# sap_flux-v22.net
KiCad netlist of a schematic drawn in EAGLE
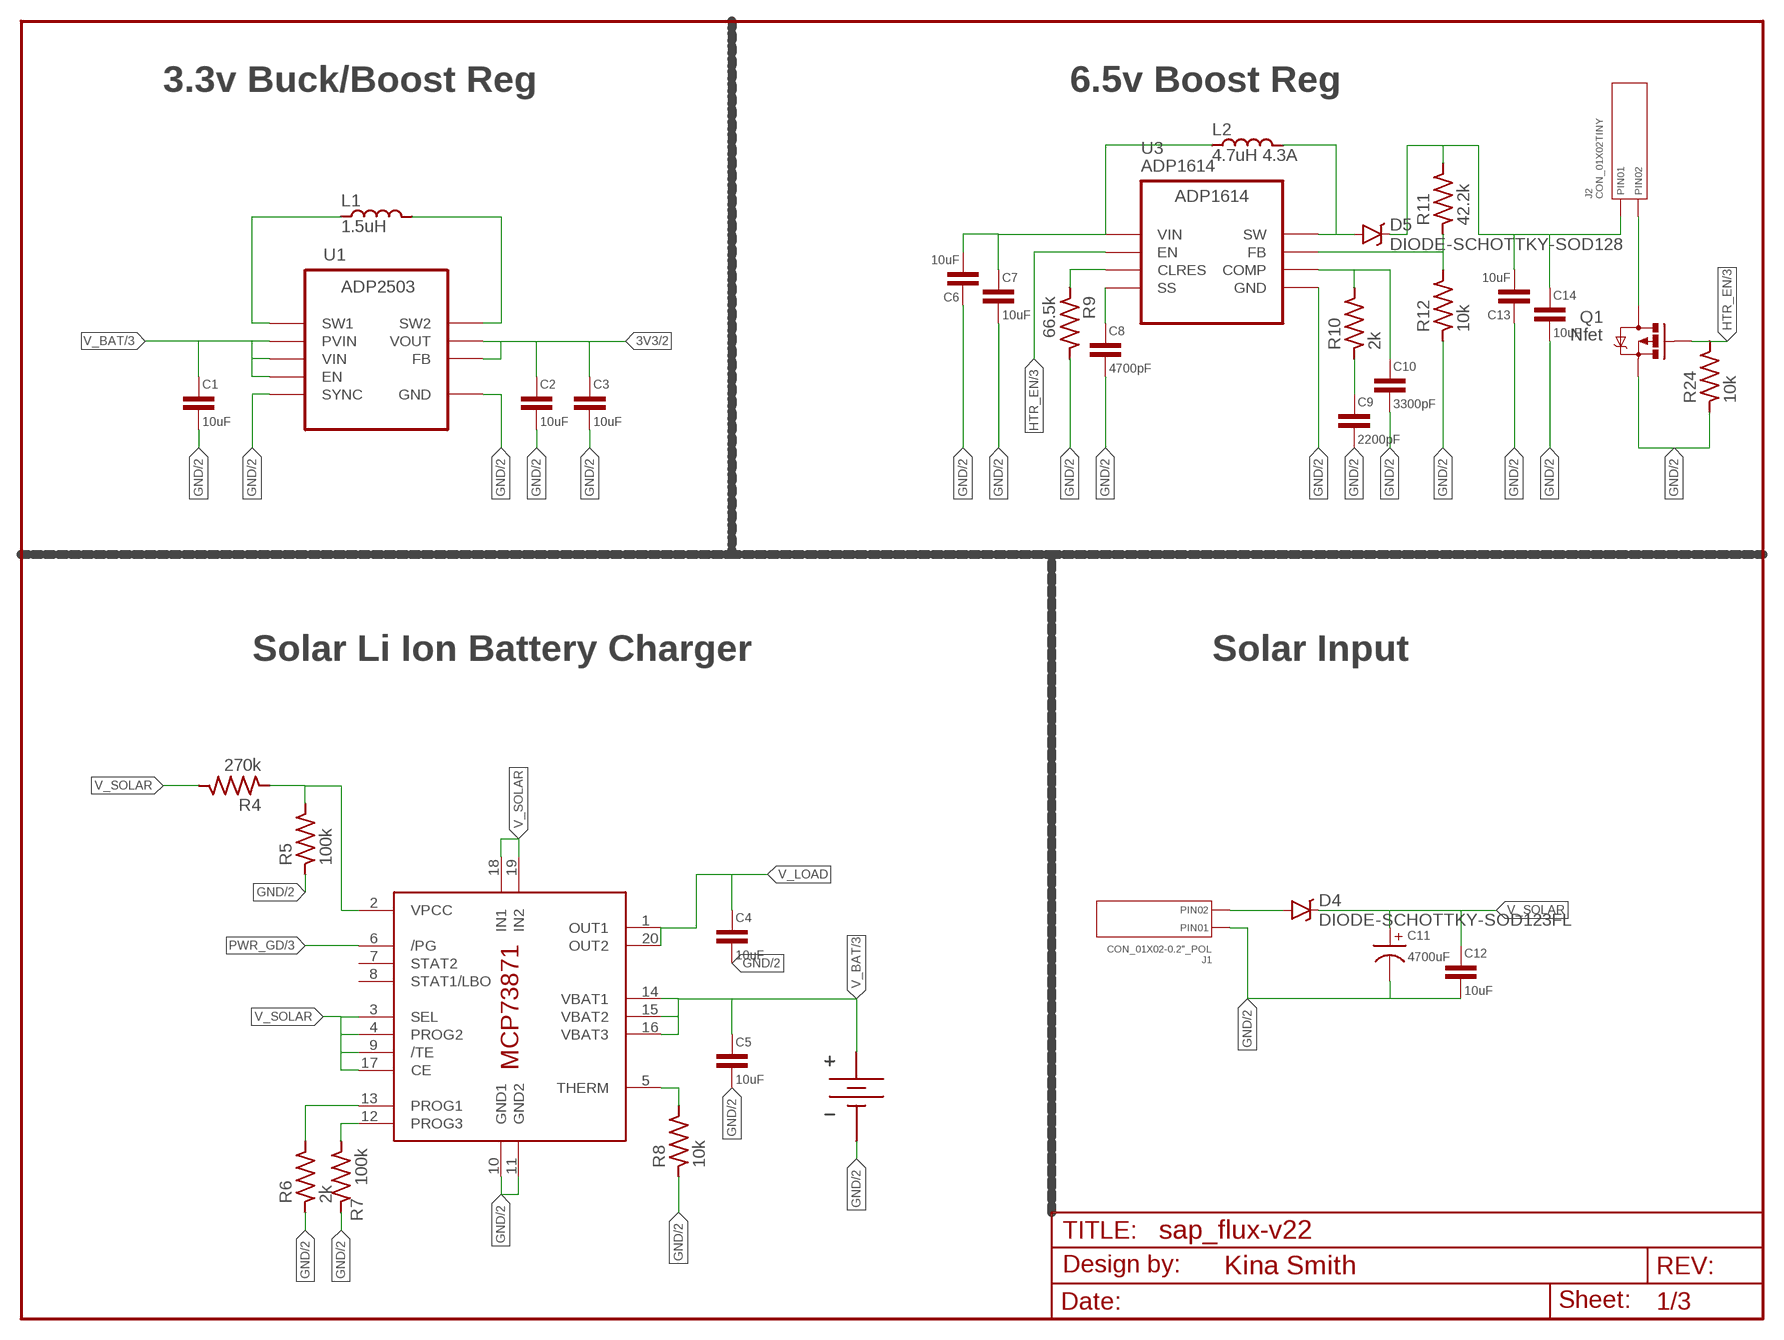
[diagram p0: schematic, sheet 1]
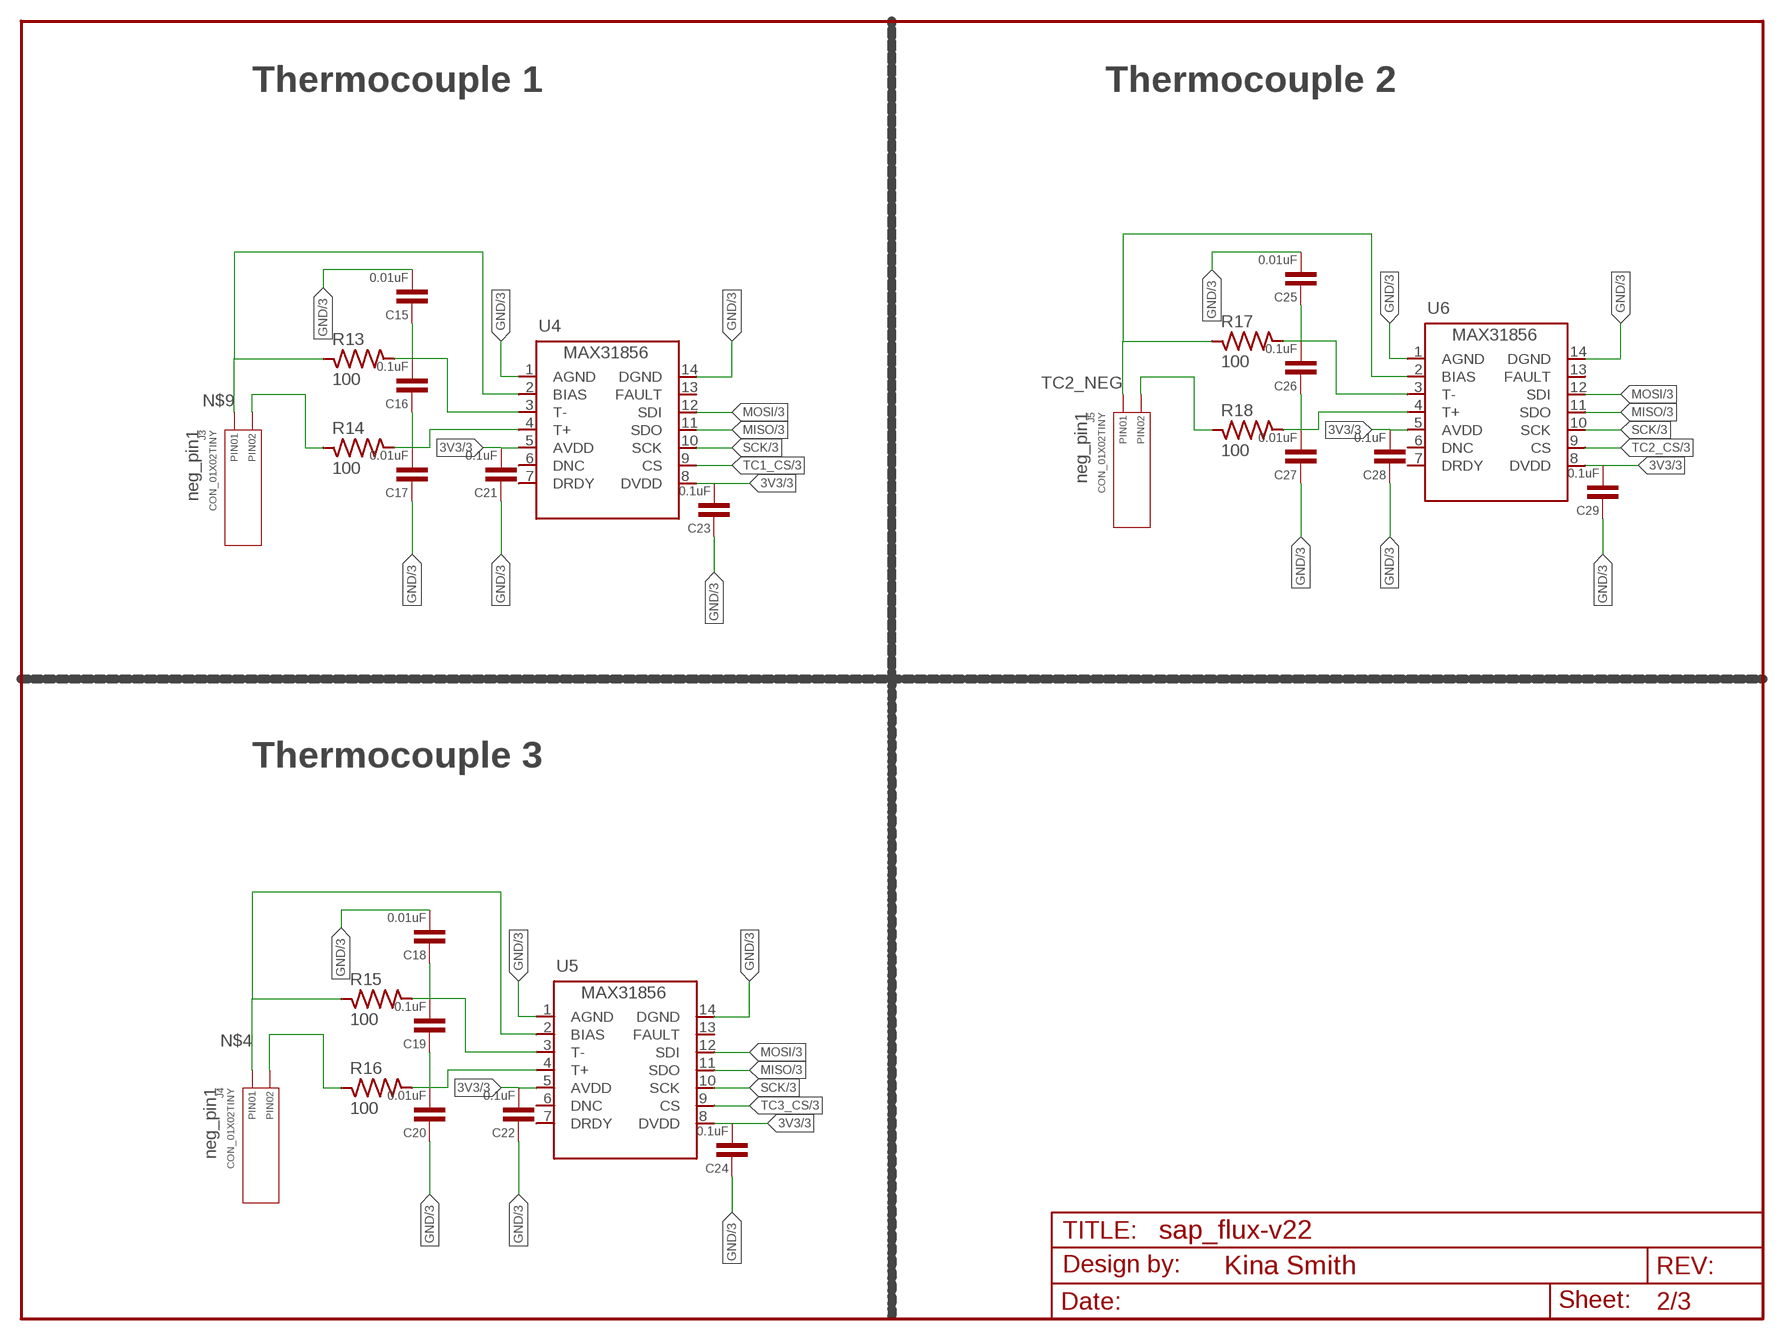
[diagram p1: schematic, sheet 2]
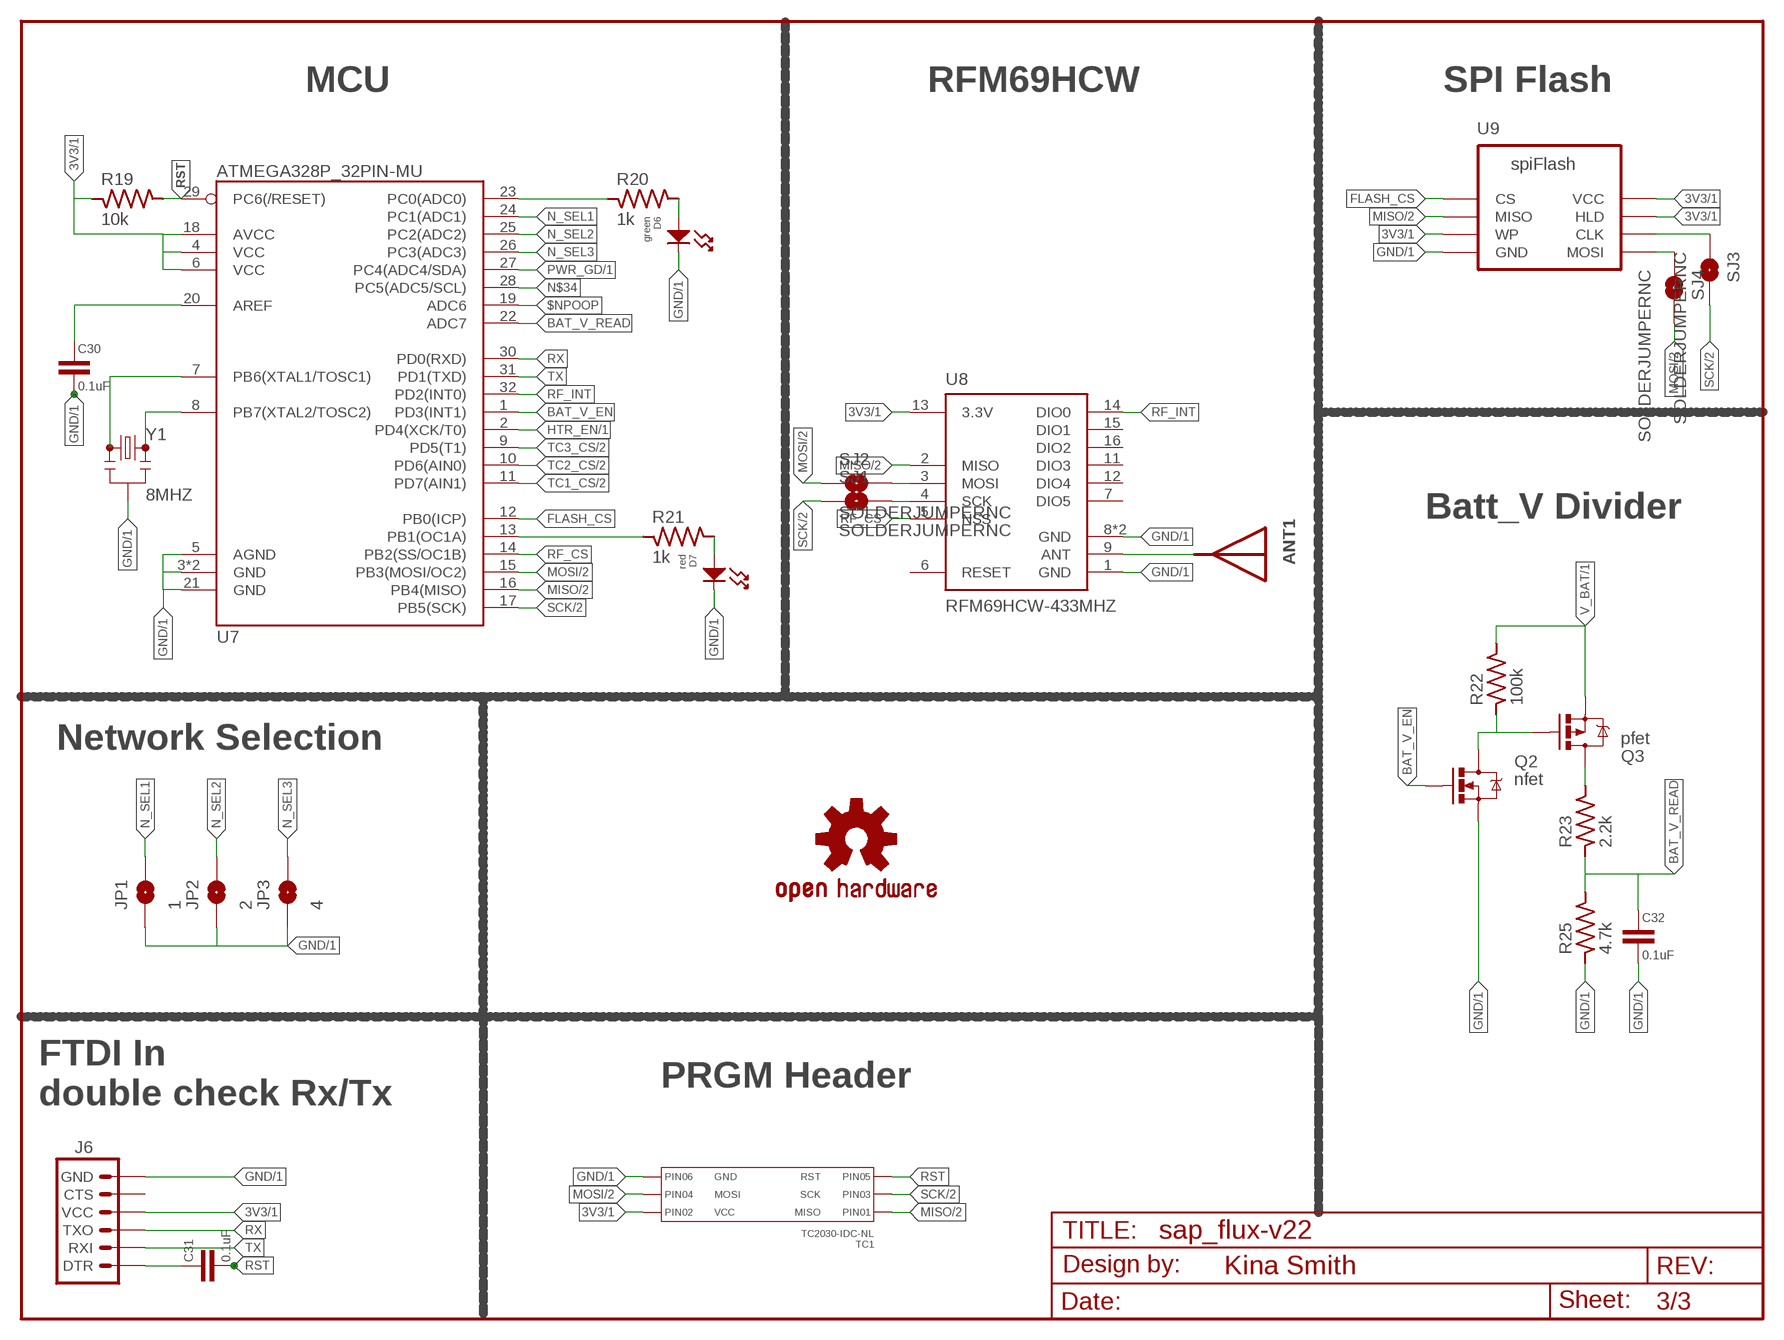
[diagram p2: schematic, sheet 3]

(export (version "E")
  (design (tool "Eeschema 10.0.6"))
  (components
    (comp (ref "BATT1")
      (value "BATTERY_HOLDER-18650_CLIP")
      (footprint "eagle-import:BAT_18650_CLIP")
      (fields (field (name "PARTNO") "54"))
      (libsource (lib "eagle-import") (part "BATTERY_HOLDER-18650_CLIP"))
    )
    (comp (ref "C1")
      (value "10uF")
      (footprint "eagle-import:C0805-N")
      (fields (field (name "PARTNO") "GRM21BR61C106KE15K"))
      (libsource (lib "eagle-import") (part "CAPACITOR_NP0805-N"))
    )
    (comp (ref "C2")
      (value "10uF")
      (footprint "eagle-import:C0805-N")
      (fields (field (name "PARTNO") "GRM21BR61C106KE15K"))
      (libsource (lib "eagle-import") (part "CAPACITOR_NP0805-N"))
    )
    (comp (ref "C3")
      (value "10uF")
      (footprint "eagle-import:C0805-N")
      (fields (field (name "PARTNO") "GRM21BR61C106KE15K"))
      (libsource (lib "eagle-import") (part "CAPACITOR_NP0805-N"))
    )
    (comp (ref "C4")
      (value "10uF")
      (footprint "eagle-import:C0805-N")
      (fields (field (name "PARTNO") "GRM21BR61C106KE15K"))
      (libsource (lib "eagle-import") (part "CAPACITOR_NP0805-N"))
    )
    (comp (ref "C5")
      (value "10uF")
      (footprint "eagle-import:C0805-N")
      (fields (field (name "PARTNO") "GRM21BR61C106KE15K"))
      (libsource (lib "eagle-import") (part "CAPACITOR_NP0805-N"))
    )
    (comp (ref "C6")
      (value "10uF")
      (footprint "eagle-import:C0805-N")
      (fields (field (name "PARTNO") "GRM21BR61C106KE15K"))
      (libsource (lib "eagle-import") (part "CAPACITOR_NP0805-N"))
    )
    (comp (ref "C7")
      (value "10uF")
      (footprint "eagle-import:C0805-N")
      (fields (field (name "PARTNO") "GRM21BR61C106KE15K"))
      (libsource (lib "eagle-import") (part "CAPACITOR_NP0805-N"))
    )
    (comp (ref "C8")
      (value "4700pF")
      (footprint "eagle-import:C0603-N")
      (fields (field (name "PARTNO") "GRM188R71C472KA01D"))
      (libsource (lib "eagle-import") (part "CAPACITOR_NP0603-N"))
    )
    (comp (ref "C9")
      (value "2200pF")
      (footprint "eagle-import:C0603-N")
      (fields (field (name "PARTNO") "GRM188R71C222KA01D"))
      (libsource (lib "eagle-import") (part "CAPACITOR_NP0603-N"))
    )
    (comp (ref "C10")
      (value "3300pF")
      (footprint "eagle-import:C0603-N")
      (fields (field (name "PARTNO") "C0603C332K4RACTU"))
      (libsource (lib "eagle-import") (part "CAPACITOR_NP0603-N"))
    )
    (comp (ref "C11")
      (value "4700uF")
      (footprint "eagle-import:CP_TH_5MM")
      (fields (field (name "PARTNO") "ECA-1AM472"))
      (libsource (lib "eagle-import") (part "CAPACITOR_P-TH_5MM"))
    )
    (comp (ref "C12")
      (value "10uF")
      (footprint "eagle-import:C0805-N")
      (fields (field (name "PARTNO") "GRM21BR61C106KE15K"))
      (libsource (lib "eagle-import") (part "CAPACITOR_NP0805-N"))
    )
    (comp (ref "C13")
      (value "10uF")
      (footprint "eagle-import:C0805-N")
      (fields (field (name "PARTNO") "GRM21BR61C106KE15K"))
      (libsource (lib "eagle-import") (part "CAPACITOR_NP0805-N"))
    )
    (comp (ref "C14")
      (value "10uF")
      (footprint "eagle-import:C0805-N")
      (fields (field (name "PARTNO") "GRM21BR61C106KE15K"))
      (libsource (lib "eagle-import") (part "CAPACITOR_NP0805-N"))
    )
    (comp (ref "D4")
      (value "DIODE-SCHOTTKY-SOD123FL")
      (footprint "eagle-import:SOD-123FL")
      (fields (field (name "PARTNO") "MBR120VLSFT1G"))
      (libsource (lib "eagle-import") (part "DIODE-SCHOTTKY-SOD123FL"))
    )
    (comp (ref "D5")
      (value "DIODE-SCHOTTKY-SOD128")
      (footprint "eagle-import:SOD128")
      (fields (field (name "PARTNO") "CMS05(TE12L,Q,M)"))
      (libsource (lib "eagle-import") (part "DIODE-SCHOTTKY-SOD128"))
    )
    (comp (ref "FRAME1")
      (value "FRAME-LETTER")
      (footprint "eagle-import:CREATIVE_COMMONS")
      (fields (field (name "PARTNO") "NA"))
      (libsource (lib "eagle-import") (part "FRAME-LETTER"))
    )
    (comp (ref "J1")
      (value "CON_01X02-0.2\"_POL")
      (footprint "eagle-import:1X02_SCREWTERM_0.2IN")
      (fields (field (name "PARTNO") "0398890042"))
      (libsource (lib "eagle-import") (part "CON_01X02-0.2{dblquote}_POL"))
    )
    (comp (ref "J2")
      (value "CON_01X02TINY")
      (footprint "eagle-import:1X02_TINY")
      (libsource (lib "eagle-import") (part "CON_01X02TINY"))
    )
    (comp (ref "L1")
      (value "1.5uH")
      (footprint "eagle-import:L3030")
      (fields (field (name "PARTNO") "NR3015T1R5N"))
      (libsource (lib "eagle-import") (part "INDUCTOR3030"))
    )
    (comp (ref "L2")
      (value "4.7uH 4.3A")
      (footprint "eagle-import:L8080")
      (fields (field (name "PARTNO") "NRS8040T100MJGJ"))
      (libsource (lib "eagle-import") (part "INDUCTOR8080"))
    )
    (comp (ref "Q1")
      (value "Nfet")
      (footprint "eagle-import:SOT23-3")
      (fields (field (name "PARTNO") "DMN2075U-7"))
      (libsource (lib "eagle-import") (part "MOSFET-PCHANNELSOT23-3"))
    )
    (comp (ref "R4")
      (value "270k")
      (footprint "eagle-import:R0603-N")
      (fields (field (name "PARTNO") "RC0603FR-07270KL"))
      (libsource (lib "eagle-import") (part "RESISTOR0603-N"))
    )
    (comp (ref "R5")
      (value "100k")
      (footprint "eagle-import:R0603-N")
      (fields (field (name "PARTNO") "RC0603FR-07100KL"))
      (libsource (lib "eagle-import") (part "RESISTOR0603-N"))
    )
    (comp (ref "R6")
      (value "2k")
      (footprint "eagle-import:R0603-N")
      (fields (field (name "PARTNO") "RC0603FR-072KL"))
      (libsource (lib "eagle-import") (part "RESISTOR0603-N"))
    )
    (comp (ref "R7")
      (value "100k")
      (footprint "eagle-import:R0603-N")
      (fields (field (name "PARTNO") "RC0603FR-07100KL"))
      (libsource (lib "eagle-import") (part "RESISTOR0603-N"))
    )
    (comp (ref "R8")
      (value "10k")
      (footprint "eagle-import:R0603-N")
      (fields (field (name "PARTNO") "RC0603FR-0710KL"))
      (libsource (lib "eagle-import") (part "RESISTOR0603-N"))
    )
    (comp (ref "R9")
      (value "66.5k")
      (footprint "eagle-import:R0603-N")
      (fields (field (name "PARTNO") "RC0603FR-0766K5L"))
      (libsource (lib "eagle-import") (part "RESISTOR0603-N"))
    )
    (comp (ref "R10")
      (value "2k")
      (footprint "eagle-import:R0603-N")
      (fields (field (name "PARTNO") "RC0603FR-072KL"))
      (libsource (lib "eagle-import") (part "RESISTOR0603-N"))
    )
    (comp (ref "R11")
      (value "42.2k")
      (footprint "eagle-import:R0603-N")
      (fields (field (name "PARTNO") "RC0603FR-0742K2L"))
      (libsource (lib "eagle-import") (part "RESISTOR0603-N"))
    )
    (comp (ref "R12")
      (value "10k")
      (footprint "eagle-import:R0603-N")
      (fields (field (name "PARTNO") "RC0603FR-0710KL"))
      (libsource (lib "eagle-import") (part "RESISTOR0603-N"))
    )
    (comp (ref "R24")
      (value "10k")
      (footprint "eagle-import:R0603-N")
      (fields (field (name "PARTNO") "RC0603FR-0710KL"))
      (libsource (lib "eagle-import") (part "RESISTOR0603-N"))
    )
    (comp (ref "U1")
      (value "ADP2503")
      (footprint "eagle-import:DFN300X300X80-11N")
      (fields (field (name "PARTNO") "ADP2503ACPZ-3.3-R7 ") (field (name "PARTNO_1") "ADP2503ACPZ-3.3-R7"))
      (libsource (lib "eagle-import") (part "ADP2503"))
    )
    (comp (ref "U2")
      (value "MCP73871")
      (footprint "eagle-import:QFN20")
      (fields (field (name "PARTNO") "MCP73871-2AAI/ML-ND"))
      (libsource (lib "eagle-import") (part "MCP73871"))
    )
    (comp (ref "U3")
      (value "ADP1614")
      (footprint "eagle-import:DFN300X300X80-11N")
      (fields (field (name "PARTNO") "ADP1614ACPZ-R7") (field (name "PARTNO_1") "ADP1614ACPZ-650-R7"))
      (libsource (lib "eagle-import") (part "ADP1614"))
    )
    (comp (ref "ANT1")
      (value "ANTENNA-433_CHIP")
      (footprint "eagle-import:ANT_433_CHIP")
      (fields (field (name "PARTNO") "0433AT62A0020E"))
      (libsource (lib "eagle-import") (part "ANTENNA-433_CHIP"))
    )
    (comp (ref "C30")
      (value "0.1uF")
      (footprint "eagle-import:C0603-N")
      (fields (field (name "PARTNO") "CC0603KRX7R7BB104"))
      (libsource (lib "eagle-import") (part "CAPACITOR_NP0603-N"))
    )
    (comp (ref "C31")
      (value "0.1uF")
      (footprint "eagle-import:C0603-N")
      (fields (field (name "PARTNO") "CC0603KRX7R7BB104"))
      (libsource (lib "eagle-import") (part "CAPACITOR_NP0603-N"))
    )
    (comp (ref "C32")
      (value "0.1uF")
      (footprint "eagle-import:C0603-N")
      (fields (field (name "PARTNO") "CC0603KRX7R7BB104"))
      (libsource (lib "eagle-import") (part "CAPACITOR_NP0603-N"))
    )
    (comp (ref "D6")
      (value "green")
      (footprint "eagle-import:LED0603")
      (fields (field (name "HOUSEPART") "NO") (field (name "PARTNO") "LTST-C191KGKT"))
      (libsource (lib "eagle-import") (part "LED_SINGLE-0603"))
    )
    (comp (ref "D7")
      (value "red")
      (footprint "eagle-import:LED0603")
      (fields (field (name "HOUSEPART") "NO") (field (name "PARTNO") "LTST-C191KRKT"))
      (libsource (lib "eagle-import") (part "LED_SINGLE-0603"))
    )
    (comp (ref "FRAME3")
      (value "FRAME-LETTERNO_PACKAGE")
      (footprint "eagle-import:DUMMY")
      (fields (field (name "PARTNO") "NA") (field (name "DESIGNER") "Nobody"))
      (libsource (lib "eagle-import") (part "FRAME-LETTERNO_PACKAGE"))
    )
    (comp (ref "J6")
      (value "ARDUINO_SERIAL_PROGRAMPTH")
      (footprint "eagle-import:1X06")
      (fields (field (name "PARTNO") "68001-106HLF"))
      (libsource (lib "eagle-import") (part "ARDUINO_SERIAL_PROGRAMPTH"))
    )
    (comp (ref "JP1")
      (value "1")
      (footprint "eagle-import:PAD-JUMPER-2-NO_YES_SILK")
      (fields (field (name "PARTNO") "NA"))
      (libsource (lib "eagle-import") (part "JUMPER-PAD-2-NOYES_SILK"))
    )
    (comp (ref "JP2")
      (value "2")
      (footprint "eagle-import:PAD-JUMPER-2-NO_YES_SILK")
      (fields (field (name "PARTNO") "NA"))
      (libsource (lib "eagle-import") (part "JUMPER-PAD-2-NOYES_SILK"))
    )
    (comp (ref "JP3")
      (value "4")
      (footprint "eagle-import:PAD-JUMPER-2-NO_YES_SILK")
      (fields (field (name "PARTNO") "NA"))
      (libsource (lib "eagle-import") (part "JUMPER-PAD-2-NOYES_SILK"))
    )
    (comp (ref "LOGO1")
      (value "OSHW-LOGOS-COPPER")
      (footprint "eagle-import:OSHW-LOGO-S_COPPER")
      (libsource (lib "eagle-import") (part "OSHW-LOGOS-COPPER"))
    )
    (comp (ref "Q2")
      (value "nfet")
      (footprint "eagle-import:SOT23-3")
      (fields (field (name "PARTNO") "BSS138"))
      (libsource (lib "eagle-import") (part "MOSFET-NCHANNELSOT23-3"))
    )
    (comp (ref "Q3")
      (value "pfet")
      (footprint "eagle-import:SOT23-3")
      (fields (field (name "PARTNO") "IRLML2244TRPBF"))
      (libsource (lib "eagle-import") (part "MOSFET-PCHANNELSOT23-3"))
    )
    (comp (ref "R19")
      (value "10k")
      (footprint "eagle-import:R0603-N")
      (fields (field (name "PARTNO") "RC0603FR-0710KL"))
      (libsource (lib "eagle-import") (part "RESISTOR0603-N"))
    )
    (comp (ref "R20")
      (value "1k")
      (footprint "eagle-import:R0603-N")
      (fields (field (name "PARTNO") "RC0603FR-071KL"))
      (libsource (lib "eagle-import") (part "RESISTOR0603-N"))
    )
    (comp (ref "R21")
      (value "1k")
      (footprint "eagle-import:R0603-N")
      (fields (field (name "PARTNO") "RC0603FR-071KL"))
      (libsource (lib "eagle-import") (part "RESISTOR0603-N"))
    )
    (comp (ref "R22")
      (value "100k")
      (footprint "eagle-import:R0603-N")
      (fields (field (name "PARTNO") "RC0603FR-07100KL"))
      (libsource (lib "eagle-import") (part "RESISTOR0603-N"))
    )
    (comp (ref "R23")
      (value "2.2k")
      (footprint "eagle-import:R0603-N")
      (fields (field (name "PARTNO") "RC0603FR-072K2L"))
      (libsource (lib "eagle-import") (part "RESISTOR0603-N"))
    )
    (comp (ref "R25")
      (value "4.7k")
      (footprint "eagle-import:R0603-N")
      (fields (field (name "PARTNO") "RC0603FR-074K7L"))
      (libsource (lib "eagle-import") (part "RESISTOR0603-N"))
    )
    (comp (ref "SJ1")
      (value "SOLDERJUMPERNC")
      (footprint "eagle-import:SJ_2S")
      (fields (field (name "PARTNO") "NA"))
      (libsource (lib "eagle-import") (part "SOLDERJUMPERNC"))
    )
    (comp (ref "SJ2")
      (value "SOLDERJUMPERNC")
      (footprint "eagle-import:SJ_2S")
      (fields (field (name "PARTNO") "NA"))
      (libsource (lib "eagle-import") (part "SOLDERJUMPERNC"))
    )
    (comp (ref "SJ3")
      (value "SOLDERJUMPERNC")
      (footprint "eagle-import:SJ_2S")
      (fields (field (name "PARTNO") "NA"))
      (libsource (lib "eagle-import") (part "SOLDERJUMPERNC"))
    )
    (comp (ref "SJ4")
      (value "SOLDERJUMPERNC")
      (footprint "eagle-import:SJ_2S")
      (fields (field (name "PARTNO") "NA"))
      (libsource (lib "eagle-import") (part "SOLDERJUMPERNC"))
    )
    (comp (ref "TC1")
      (value "TC2030-IDC-NL")
      (footprint "eagle-import:TC2030-IDC-NL")
      (fields (field (name "HOUSEPART") "NO") (field (name "PARTNO") "NA"))
      (libsource (lib "eagle-import") (part "CON_02X03_TC2030-IDC-NL_AVRISP"))
    )
    (comp (ref "U7")
      (value "ATMEGA328P_32PIN-MU")
      (footprint "eagle-import:MLF32_RECTPADS")
      (fields (field (name "PARTNO") "ATMEGA328P-MU"))
      (libsource (lib "eagle-import") (part "ATMEGA328P_32PIN-MU"))
    )
    (comp (ref "U8")
      (value "RFM69HCW-433MHZ")
      (footprint "eagle-import:RFM69HCW-XXXS2")
      (fields (field (name "PARTNO") "COM-13910"))
      (libsource (lib "eagle-import") (part "RFM69HCW-433MHZ"))
    )
    (comp (ref "U9")
      (value "WINBOND_FLASH_4MBIT-SOIC")
      (footprint "eagle-import:SOIC8")
      (fields (field (name "PARTNO") "W25X40CLSNIG"))
      (libsource (lib "eagle-import") (part "WINBOND_FLASH_4MBIT-SOIC"))
    )
    (comp (ref "Y1")
      (value "8MHZ")
      (footprint "eagle-import:RESONATOR-SMD")
      (fields (field (name "PARTNO") "CSTCE8M00G55-R0"))
      (libsource (lib "eagle-import") (part "RESONATOR8MHZ"))
    )
    (comp (ref "C15")
      (value "0.01uF")
      (footprint "eagle-import:C0603-N")
      (fields (field (name "PARTNO") "GRM188R71C103KA01D"))
      (libsource (lib "eagle-import") (part "CAPACITOR_NP0603-N"))
    )
    (comp (ref "C16")
      (value "0.1uF")
      (footprint "eagle-import:C0603-N")
      (fields (field (name "PARTNO") "CC0603KRX7R7BB104"))
      (libsource (lib "eagle-import") (part "CAPACITOR_NP0603-N"))
    )
    (comp (ref "C17")
      (value "0.01uF")
      (footprint "eagle-import:C0603-N")
      (fields (field (name "PARTNO") "GRM188R71C103KA01D"))
      (libsource (lib "eagle-import") (part "CAPACITOR_NP0603-N"))
    )
    (comp (ref "C18")
      (value "0.01uF")
      (footprint "eagle-import:C0603-N")
      (fields (field (name "PARTNO") "GRM188R71C103KA01D"))
      (libsource (lib "eagle-import") (part "CAPACITOR_NP0603-N"))
    )
    (comp (ref "C19")
      (value "0.1uF")
      (footprint "eagle-import:C0603-N")
      (fields (field (name "PARTNO") "CC0603KRX7R7BB104"))
      (libsource (lib "eagle-import") (part "CAPACITOR_NP0603-N"))
    )
    (comp (ref "C20")
      (value "0.01uF")
      (footprint "eagle-import:C0603-N")
      (fields (field (name "PARTNO") "GRM188R71C103KA01D"))
      (libsource (lib "eagle-import") (part "CAPACITOR_NP0603-N"))
    )
    (comp (ref "C21")
      (value "0.1uF")
      (footprint "eagle-import:C0603-N")
      (fields (field (name "PARTNO") "CC0603KRX7R7BB104"))
      (libsource (lib "eagle-import") (part "CAPACITOR_NP0603-N"))
    )
    (comp (ref "C22")
      (value "0.1uF")
      (footprint "eagle-import:C0603-N")
      (fields (field (name "PARTNO") "CC0603KRX7R7BB104"))
      (libsource (lib "eagle-import") (part "CAPACITOR_NP0603-N"))
    )
    (comp (ref "C23")
      (value "0.1uF")
      (footprint "eagle-import:C0603-N")
      (fields (field (name "PARTNO") "CC0603KRX7R7BB104"))
      (libsource (lib "eagle-import") (part "CAPACITOR_NP0603-N"))
    )
    (comp (ref "C24")
      (value "0.1uF")
      (footprint "eagle-import:C0603-N")
      (fields (field (name "PARTNO") "CC0603KRX7R7BB104"))
      (libsource (lib "eagle-import") (part "CAPACITOR_NP0603-N"))
    )
    (comp (ref "C25")
      (value "0.01uF")
      (footprint "eagle-import:C0603-N")
      (fields (field (name "PARTNO") "GRM188R71C103KA01D"))
      (libsource (lib "eagle-import") (part "CAPACITOR_NP0603-N"))
    )
    (comp (ref "C26")
      (value "0.1uF")
      (footprint "eagle-import:C0603-N")
      (fields (field (name "PARTNO") "CC0603KRX7R7BB104"))
      (libsource (lib "eagle-import") (part "CAPACITOR_NP0603-N"))
    )
    (comp (ref "C27")
      (value "0.01uF")
      (footprint "eagle-import:C0603-N")
      (fields (field (name "PARTNO") "GRM188R71C103KA01D"))
      (libsource (lib "eagle-import") (part "CAPACITOR_NP0603-N"))
    )
    (comp (ref "C28")
      (value "0.1uF")
      (footprint "eagle-import:C0603-N")
      (fields (field (name "PARTNO") "CC0603KRX7R7BB104"))
      (libsource (lib "eagle-import") (part "CAPACITOR_NP0603-N"))
    )
    (comp (ref "C29")
      (value "0.1uF")
      (footprint "eagle-import:C0603-N")
      (fields (field (name "PARTNO") "CC0603KRX7R7BB104"))
      (libsource (lib "eagle-import") (part "CAPACITOR_NP0603-N"))
    )
    (comp (ref "FRAME2")
      (value "FRAME-LETTERNO_PACKAGE")
      (footprint "eagle-import:DUMMY")
      (fields (field (name "PARTNO") "NA") (field (name "DESIGNER") "Nobody"))
      (libsource (lib "eagle-import") (part "FRAME-LETTERNO_PACKAGE"))
    )
    (comp (ref "J3")
      (value "CON_01X02TINY")
      (footprint "eagle-import:1X02_TINY")
      (fields (field (name "NOTE") "neg_pin1"))
      (libsource (lib "eagle-import") (part "CON_01X02TINY"))
    )
    (comp (ref "J4")
      (value "CON_01X02TINY")
      (footprint "eagle-import:1X02_TINY")
      (fields (field (name "NOTE") "neg_pin1"))
      (libsource (lib "eagle-import") (part "CON_01X02TINY"))
    )
    (comp (ref "J5")
      (value "CON_01X02TINY")
      (footprint "eagle-import:1X02_TINY")
      (fields (field (name "NOTE") "neg_pin1"))
      (libsource (lib "eagle-import") (part "CON_01X02TINY"))
    )
    (comp (ref "R13")
      (value "100")
      (footprint "eagle-import:R0603-N")
      (fields (field (name "PARTNO") "RC0603FR-07100RL"))
      (libsource (lib "eagle-import") (part "RESISTOR0603-N"))
    )
    (comp (ref "R14")
      (value "100")
      (footprint "eagle-import:R0603-N")
      (fields (field (name "PARTNO") "RC0603FR-07100RL"))
      (libsource (lib "eagle-import") (part "RESISTOR0603-N"))
    )
    (comp (ref "R15")
      (value "100")
      (footprint "eagle-import:R0603-N")
      (fields (field (name "PARTNO") "RC0603FR-07100RL"))
      (libsource (lib "eagle-import") (part "RESISTOR0603-N"))
    )
    (comp (ref "R16")
      (value "100")
      (footprint "eagle-import:R0603-N")
      (fields (field (name "PARTNO") "RC0603FR-07100RL"))
      (libsource (lib "eagle-import") (part "RESISTOR0603-N"))
    )
    (comp (ref "R17")
      (value "100")
      (footprint "eagle-import:R0603-N")
      (fields (field (name "PARTNO") "RC0603FR-07100RL"))
      (libsource (lib "eagle-import") (part "RESISTOR0603-N"))
    )
    (comp (ref "R18")
      (value "100")
      (footprint "eagle-import:R0603-N")
      (fields (field (name "PARTNO") "RC0603FR-07100RL"))
      (libsource (lib "eagle-import") (part "RESISTOR0603-N"))
    )
    (comp (ref "U4")
      (value "MAX31856MUD+")
      (footprint "eagle-import:TSSOP14")
      (libsource (lib "eagle-import") (part "MAX31856MUD+"))
    )
    (comp (ref "U5")
      (value "MAX31856MUD+")
      (footprint "eagle-import:TSSOP14")
      (libsource (lib "eagle-import") (part "MAX31856MUD+"))
    )
    (comp (ref "U6")
      (value "MAX31856MUD+")
      (footprint "eagle-import:TSSOP14")
      (libsource (lib "eagle-import") (part "MAX31856MUD+"))
    )
  )
  (nets
    (net (code "1") (name "$NPOOP") (class "Default")
      (node (ref "U7") (pin "19") (pinfunction "ADC6_19") (pintype "bidirectional"))
    )
    (net (code "2") (name "3V3") (class "Default")
      (node (ref "C2") (pin "1") (pinfunction "1_1") (pintype "passive"))
      (node (ref "C21") (pin "2") (pinfunction "2_2") (pintype "passive"))
      (node (ref "C22") (pin "2") (pinfunction "2_2") (pintype "passive"))
      (node (ref "C23") (pin "2") (pinfunction "2_2") (pintype "passive"))
      (node (ref "C24") (pin "2") (pinfunction "2_2") (pintype "passive"))
      (node (ref "C28") (pin "2") (pinfunction "2_2") (pintype "passive"))
      (node (ref "C29") (pin "2") (pinfunction "2_2") (pintype "passive"))
      (node (ref "C3") (pin "1") (pinfunction "1_1") (pintype "passive"))
      (node (ref "J6") (pin "4") (pinfunction "VCC_4") (pintype "passive"))
      (node (ref "R19") (pin "1") (pinfunction "P$1_1") (pintype "passive"))
      (node (ref "TC1") (pin "P$2") (pinfunction "PIN2_P$2") (pintype "bidirectional"))
      (node (ref "U1") (pin "1") (pinfunction "VOUT_1") (pintype "bidirectional"))
      (node (ref "U1") (pin "10") (pinfunction "FB_10") (pintype "bidirectional"))
      (node (ref "U4") (pin "5") (pinfunction "AVDD_5") (pintype "bidirectional"))
      (node (ref "U4") (pin "8") (pinfunction "DVDD_8") (pintype "bidirectional"))
      (node (ref "U5") (pin "5") (pinfunction "AVDD_5") (pintype "bidirectional"))
      (node (ref "U5") (pin "8") (pinfunction "DVDD_8") (pintype "bidirectional"))
      (node (ref "U6") (pin "5") (pinfunction "AVDD_5") (pintype "bidirectional"))
      (node (ref "U6") (pin "8") (pinfunction "DVDD_8") (pintype "bidirectional"))
      (node (ref "U7") (pin "18") (pinfunction "AVCC_18") (pintype "bidirectional"))
      (node (ref "U7") (pin "4") (pinfunction "VCC_4") (pintype "bidirectional"))
      (node (ref "U7") (pin "6") (pinfunction "VCC_6") (pintype "bidirectional"))
      (node (ref "U8") (pin "13") (pinfunction "3.3V_13") (pintype "power_in"))
      (node (ref "U9") (pin "3") (pinfunction "WP_3") (pintype "bidirectional"))
      (node (ref "U9") (pin "7") (pinfunction "HLD_7") (pintype "bidirectional"))
      (node (ref "U9") (pin "8") (pinfunction "VCC_8") (pintype "bidirectional"))
    )
    (net (code "3") (name "BAT_V_EN") (class "Default")
      (node (ref "Q2") (pin "1") (pinfunction "G_1") (pintype "passive"))
      (node (ref "U7") (pin "1") (pinfunction "PD3(INT1)_1") (pintype "bidirectional"))
    )
    (net (code "4") (name "BAT_V_READ") (class "Default")
      (node (ref "C32") (pin "1") (pinfunction "1_1") (pintype "passive"))
      (node (ref "R23") (pin "1") (pinfunction "P$1_1") (pintype "passive"))
      (node (ref "R25") (pin "2") (pinfunction "P$2_2") (pintype "passive"))
      (node (ref "U7") (pin "22") (pinfunction "ADC7_22") (pintype "bidirectional"))
    )
    (net (code "5") (name "FLASH_CS") (class "Default")
      (node (ref "U7") (pin "12") (pinfunction "PB0(ICP)_12") (pintype "bidirectional"))
      (node (ref "U9") (pin "1") (pinfunction "CS_1") (pintype "bidirectional"))
    )
    (net (code "6") (name "GND") (class "Default")
      (node (ref "BATT1") (pin "NEG_1") (pinfunction "GND_NEG_1") (pintype "bidirectional"))
      (node (ref "BATT1") (pin "NEG_2") (pinfunction "GND_NEG_2") (pintype "bidirectional"))
      (node (ref "BATT1") (pin "NEG_3") (pinfunction "GND_NEG_3") (pintype "bidirectional"))
      (node (ref "C1") (pin "2") (pinfunction "2_2") (pintype "passive"))
      (node (ref "C10") (pin "2") (pinfunction "2_2") (pintype "passive"))
      (node (ref "C11") (pin "NEG") (pinfunction "NEG_NEG") (pintype "passive"))
      (node (ref "C12") (pin "2") (pinfunction "2_2") (pintype "passive"))
      (node (ref "C13") (pin "1") (pinfunction "1_1") (pintype "passive"))
      (node (ref "C14") (pin "2") (pinfunction "2_2") (pintype "passive"))
      (node (ref "C15") (pin "2") (pinfunction "2_2") (pintype "passive"))
      (node (ref "C17") (pin "1") (pinfunction "1_1") (pintype "passive"))
      (node (ref "C18") (pin "2") (pinfunction "2_2") (pintype "passive"))
      (node (ref "C2") (pin "2") (pinfunction "2_2") (pintype "passive"))
      (node (ref "C20") (pin "1") (pinfunction "1_1") (pintype "passive"))
      (node (ref "C21") (pin "1") (pinfunction "1_1") (pintype "passive"))
      (node (ref "C22") (pin "1") (pinfunction "1_1") (pintype "passive"))
      (node (ref "C23") (pin "1") (pinfunction "1_1") (pintype "passive"))
      (node (ref "C24") (pin "1") (pinfunction "1_1") (pintype "passive"))
      (node (ref "C25") (pin "2") (pinfunction "2_2") (pintype "passive"))
      (node (ref "C27") (pin "1") (pinfunction "1_1") (pintype "passive"))
      (node (ref "C28") (pin "1") (pinfunction "1_1") (pintype "passive"))
      (node (ref "C29") (pin "1") (pinfunction "1_1") (pintype "passive"))
      (node (ref "C3") (pin "2") (pinfunction "2_2") (pintype "passive"))
      (node (ref "C30") (pin "2") (pinfunction "2_2") (pintype "passive"))
      (node (ref "C32") (pin "2") (pinfunction "2_2") (pintype "passive"))
      (node (ref "C4") (pin "2") (pinfunction "2_2") (pintype "passive"))
      (node (ref "C5") (pin "2") (pinfunction "2_2") (pintype "passive"))
      (node (ref "C6") (pin "1") (pinfunction "1_1") (pintype "passive"))
      (node (ref "C7") (pin "2") (pinfunction "2_2") (pintype "passive"))
      (node (ref "C8") (pin "2") (pinfunction "2_2") (pintype "passive"))
      (node (ref "C9") (pin "2") (pinfunction "2_2") (pintype "passive"))
      (node (ref "D6") (pin "CATHODE") (pinfunction "CATHODE_CATHODE") (pintype "power_in"))
      (node (ref "D7") (pin "CATHODE") (pinfunction "CATHODE_CATHODE") (pintype "power_in"))
      (node (ref "J1") (pin "NEG") (pinfunction "PIN1_NEG") (pintype "bidirectional"))
      (node (ref "J6") (pin "6") (pinfunction "GND_6") (pintype "passive"))
      (node (ref "JP1") (pin "1") (pinfunction "1_1") (pintype "passive"))
      (node (ref "JP2") (pin "1") (pinfunction "1_1") (pintype "passive"))
      (node (ref "JP3") (pin "1") (pinfunction "1_1") (pintype "passive"))
      (node (ref "Q1") (pin "2") (pinfunction "S_2") (pintype "passive"))
      (node (ref "Q2") (pin "2") (pinfunction "S_2") (pintype "passive"))
      (node (ref "R12") (pin "1") (pinfunction "P$1_1") (pintype "passive"))
      (node (ref "R24") (pin "1") (pinfunction "P$1_1") (pintype "passive"))
      (node (ref "R25") (pin "1") (pinfunction "P$1_1") (pintype "passive"))
      (node (ref "R5") (pin "1") (pinfunction "P$1_1") (pintype "passive"))
      (node (ref "R6") (pin "1") (pinfunction "P$1_1") (pintype "passive"))
      (node (ref "R7") (pin "1") (pinfunction "P$1_1") (pintype "passive"))
      (node (ref "R8") (pin "1") (pinfunction "P$1_1") (pintype "passive"))
      (node (ref "R9") (pin "2") (pinfunction "P$2_2") (pintype "passive"))
      (node (ref "TC1") (pin "P$6") (pinfunction "PIN6_P$6") (pintype "bidirectional"))
      (node (ref "U1") (pin "11") (pinfunction "GND_11") (pintype "bidirectional"))
      (node (ref "U1") (pin "3") (pinfunction "GND_3") (pintype "bidirectional"))
      (node (ref "U1") (pin "7") (pinfunction "SYNC_7") (pintype "bidirectional"))
      (node (ref "U1") (pin "9") (pinfunction "GND_9") (pintype "bidirectional"))
      (node (ref "U2") (pin "10") (pinfunction "GND1_10") (pintype "power_in"))
      (node (ref "U2") (pin "11") (pinfunction "GND2_11") (pintype "power_in"))
      (node (ref "U3") (pin "11") (pinfunction "GND_11") (pintype "bidirectional"))
      (node (ref "U3") (pin "4") (pinfunction "GND_4") (pintype "bidirectional"))
      (node (ref "U3") (pin "5") (pinfunction "GND_5") (pintype "bidirectional"))
      (node (ref "U4") (pin "1") (pinfunction "AGND_1") (pintype "bidirectional"))
      (node (ref "U4") (pin "14") (pinfunction "DGND_14") (pintype "bidirectional"))
      (node (ref "U5") (pin "1") (pinfunction "AGND_1") (pintype "bidirectional"))
      (node (ref "U5") (pin "14") (pinfunction "DGND_14") (pintype "bidirectional"))
      (node (ref "U6") (pin "1") (pinfunction "AGND_1") (pintype "bidirectional"))
      (node (ref "U6") (pin "14") (pinfunction "DGND_14") (pintype "bidirectional"))
      (node (ref "U7") (pin "21") (pinfunction "GND_21") (pintype "bidirectional"))
      (node (ref "U7") (pin "3") (pinfunction "GND_3") (pintype "bidirectional"))
      (node (ref "U7") (pin "5") (pinfunction "AGND_5") (pintype "bidirectional"))
      (node (ref "U7") (pin "PAD") (pinfunction "GND_PAD") (pintype "bidirectional"))
      (node (ref "U8") (pin "1") (pinfunction "GND_1") (pintype "power_in"))
      (node (ref "U8") (pin "10") (pinfunction "GND_10") (pintype "power_in"))
      (node (ref "U8") (pin "8") (pinfunction "GND_8") (pintype "power_in"))
      (node (ref "U9") (pin "4") (pinfunction "GND_4") (pintype "bidirectional"))
      (node (ref "Y1") (pin "2") (pinfunction "2_2") (pintype "passive"))
    )
    (net (code "7") (name "HTR_EN") (class "Default")
      (node (ref "Q1") (pin "1") (pinfunction "G_1") (pintype "passive"))
      (node (ref "R24") (pin "2") (pinfunction "P$2_2") (pintype "passive"))
      (node (ref "U3") (pin "3") (pinfunction "EN_3") (pintype "bidirectional"))
      (node (ref "U7") (pin "2") (pinfunction "PD4(XCK/T0)_2") (pintype "bidirectional"))
    )
    (net (code "8") (name "MISO") (class "Default")
      (node (ref "TC1") (pin "P$1") (pinfunction "PIN1_P$1") (pintype "bidirectional"))
      (node (ref "U4") (pin "11") (pinfunction "SDO_11") (pintype "bidirectional"))
      (node (ref "U5") (pin "11") (pinfunction "SDO_11") (pintype "bidirectional"))
      (node (ref "U6") (pin "11") (pinfunction "SDO_11") (pintype "bidirectional"))
      (node (ref "U7") (pin "16") (pinfunction "PB4(MISO)_16") (pintype "bidirectional"))
      (node (ref "U8") (pin "2") (pinfunction "MISO_2") (pintype "bidirectional"))
      (node (ref "U9") (pin "2") (pinfunction "MISO_2") (pintype "bidirectional"))
    )
    (net (code "9") (name "MOSI") (class "Default")
      (node (ref "SJ2") (pin "1") (pinfunction "1_1") (pintype "passive"))
      (node (ref "SJ4") (pin "2") (pinfunction "2_2") (pintype "passive"))
      (node (ref "TC1") (pin "P$4") (pinfunction "PIN4_P$4") (pintype "bidirectional"))
      (node (ref "U4") (pin "12") (pinfunction "SDI_12") (pintype "bidirectional"))
      (node (ref "U5") (pin "12") (pinfunction "SDI_12") (pintype "bidirectional"))
      (node (ref "U6") (pin "12") (pinfunction "SDI_12") (pintype "bidirectional"))
      (node (ref "U7") (pin "15") (pinfunction "PB3(MOSI/OC2)_15") (pintype "bidirectional"))
    )
    (net (code "10") (name "N$4") (class "Default")
      (node (ref "J4") (pin "NEG") (pinfunction "PIN1_NEG") (pintype "bidirectional"))
      (node (ref "R15") (pin "1") (pinfunction "P$1_1") (pintype "passive"))
      (node (ref "U5") (pin "2") (pinfunction "BIAS_2") (pintype "bidirectional"))
    )
    (net (code "11") (name "N$9") (class "Default")
      (node (ref "J3") (pin "NEG") (pinfunction "PIN1_NEG") (pintype "bidirectional"))
      (node (ref "R13") (pin "1") (pinfunction "P$1_1") (pintype "passive"))
      (node (ref "U4") (pin "2") (pinfunction "BIAS_2") (pintype "bidirectional"))
    )
    (net (code "12") (name "N$34") (class "Default")
      (node (ref "U7") (pin "28") (pinfunction "PC5(ADC5/SCL)_28") (pintype "bidirectional"))
    )
    (net (code "13") (name "N_SEL1") (class "Default")
      (node (ref "JP1") (pin "2") (pinfunction "2_2") (pintype "passive"))
      (node (ref "U7") (pin "24") (pinfunction "PC1(ADC1)_24") (pintype "bidirectional"))
    )
    (net (code "14") (name "N_SEL2") (class "Default")
      (node (ref "JP2") (pin "2") (pinfunction "2_2") (pintype "passive"))
      (node (ref "U7") (pin "25") (pinfunction "PC2(ADC2)_25") (pintype "bidirectional"))
    )
    (net (code "15") (name "N_SEL3") (class "Default")
      (node (ref "JP3") (pin "2") (pinfunction "2_2") (pintype "passive"))
      (node (ref "U7") (pin "26") (pinfunction "PC3(ADC3)_26") (pintype "bidirectional"))
    )
    (net (code "16") (name "Net-(D5-A)") (class "Default")
      (node (ref "D5") (pin "A-2") (pinfunction "A_A-2") (pintype "passive"))
      (node (ref "L2") (pin "2") (pinfunction "P$2_2") (pintype "passive"))
      (node (ref "U3") (pin "6") (pinfunction "SW_6") (pintype "bidirectional"))
      (node (ref "U3") (pin "7") (pinfunction "SW_7") (pintype "bidirectional"))
    )
    (net (code "17") (name "Net-(D5-C)") (class "Default")
      (node (ref "C13") (pin "2") (pinfunction "2_2") (pintype "passive"))
      (node (ref "C14") (pin "1") (pinfunction "1_1") (pintype "passive"))
      (node (ref "D5") (pin "C-1") (pinfunction "C_C-1") (pintype "passive"))
      (node (ref "J2") (pin "NEG") (pinfunction "PIN1_NEG") (pintype "bidirectional"))
      (node (ref "R11") (pin "2") (pinfunction "P$2_2") (pintype "passive"))
    )
    (net (code "18") (name "Net-(J1-PIN2)") (class "Default")
      (node (ref "D4") (pin "A") (pinfunction "A_A") (pintype "passive"))
      (node (ref "J1") (pin "POS") (pinfunction "PIN2_POS") (pintype "bidirectional"))
    )
    (net (code "19") (name "Net-(J2-PIN2)") (class "Default")
      (node (ref "J2") (pin "POS") (pinfunction "PIN2_POS") (pintype "bidirectional"))
      (node (ref "Q1") (pin "3") (pinfunction "D_3") (pintype "passive"))
    )
    (net (code "20") (name "Net-(J3-PIN2)") (class "Default")
      (node (ref "J3") (pin "POS") (pinfunction "PIN2_POS") (pintype "bidirectional"))
      (node (ref "R14") (pin "1") (pinfunction "P$1_1") (pintype "passive"))
    )
    (net (code "21") (name "Net-(J4-PIN2)") (class "Default")
      (node (ref "J4") (pin "POS") (pinfunction "PIN2_POS") (pintype "bidirectional"))
      (node (ref "R16") (pin "1") (pinfunction "P$1_1") (pintype "passive"))
    )
    (net (code "22") (name "Net-(J5-PIN2)") (class "Default")
      (node (ref "J5") (pin "POS") (pinfunction "PIN2_POS") (pintype "bidirectional"))
      (node (ref "R18") (pin "1") (pinfunction "P$1_1") (pintype "passive"))
    )
    (net (code "23") (name "Net-(J6-DTR)") (class "Default")
      (node (ref "C31") (pin "1") (pinfunction "1_1") (pintype "passive"))
      (node (ref "J6") (pin "1") (pinfunction "DTR_1") (pintype "passive"))
    )
    (net (code "24") (name "Net-(Q2-D)") (class "Default")
      (node (ref "Q2") (pin "3") (pinfunction "D_3") (pintype "passive"))
      (node (ref "Q3") (pin "1") (pinfunction "G_1") (pintype "passive"))
      (node (ref "R22") (pin "1") (pinfunction "P$1_1") (pintype "passive"))
    )
    (net (code "25") (name "Net-(Q3-D)") (class "Default")
      (node (ref "Q3") (pin "3") (pinfunction "D_3") (pintype "passive"))
      (node (ref "R23") (pin "2") (pinfunction "P$2_2") (pintype "passive"))
    )
    (net (code "26") (name "Net-(R4-P$1)") (class "Default")
      (node (ref "R4") (pin "1") (pinfunction "P$1_1") (pintype "passive"))
      (node (ref "R5") (pin "2") (pinfunction "P$2_2") (pintype "passive"))
      (node (ref "U2") (pin "2") (pinfunction "VPCC_2") (pintype "input"))
    )
    (net (code "27") (name "Net-(R6-P$2)") (class "Default")
      (node (ref "R6") (pin "2") (pinfunction "P$2_2") (pintype "passive"))
      (node (ref "U2") (pin "13") (pinfunction "PROG1_13") (pintype "input"))
    )
    (net (code "28") (name "Net-(R7-P$2)") (class "Default")
      (node (ref "R7") (pin "2") (pinfunction "P$2_2") (pintype "passive"))
      (node (ref "U2") (pin "12") (pinfunction "PROG3_12") (pintype "input"))
    )
    (net (code "29") (name "Net-(R8-P$2)") (class "Default")
      (node (ref "R8") (pin "2") (pinfunction "P$2_2") (pintype "passive"))
      (node (ref "U2") (pin "5") (pinfunction "THERM_5") (pintype "input"))
    )
    (net (code "30") (name "Net-(R9-P$1)") (class "Default")
      (node (ref "R9") (pin "1") (pinfunction "P$1_1") (pintype "passive"))
      (node (ref "U3") (pin "9") (pinfunction "CLRES_9") (pintype "bidirectional"))
    )
    (net (code "31") (name "Net-(R10-P$1)") (class "Default")
      (node (ref "C9") (pin "1") (pinfunction "1_1") (pintype "passive"))
      (node (ref "R10") (pin "1") (pinfunction "P$1_1") (pintype "passive"))
    )
    (net (code "32") (name "Net-(R10-P$2)") (class "Default")
      (node (ref "C10") (pin "1") (pinfunction "1_1") (pintype "passive"))
      (node (ref "R10") (pin "2") (pinfunction "P$2_2") (pintype "passive"))
      (node (ref "U3") (pin "1") (pinfunction "COMP_1") (pintype "bidirectional"))
    )
    (net (code "33") (name "Net-(R11-P$1)") (class "Default")
      (node (ref "R11") (pin "1") (pinfunction "P$1_1") (pintype "passive"))
      (node (ref "R12") (pin "2") (pinfunction "P$2_2") (pintype "passive"))
      (node (ref "U3") (pin "2") (pinfunction "FB_2") (pintype "bidirectional"))
    )
    (net (code "34") (name "Net-(R13-P$2)") (class "Default")
      (node (ref "C15") (pin "1") (pinfunction "1_1") (pintype "passive"))
      (node (ref "C16") (pin "2") (pinfunction "2_2") (pintype "passive"))
      (node (ref "R13") (pin "2") (pinfunction "P$2_2") (pintype "passive"))
      (node (ref "U4") (pin "3") (pinfunction "T-_3") (pintype "bidirectional"))
    )
    (net (code "35") (name "Net-(R14-P$2)") (class "Default")
      (node (ref "C16") (pin "1") (pinfunction "1_1") (pintype "passive"))
      (node (ref "C17") (pin "2") (pinfunction "2_2") (pintype "passive"))
      (node (ref "R14") (pin "2") (pinfunction "P$2_2") (pintype "passive"))
      (node (ref "U4") (pin "4") (pinfunction "T+_4") (pintype "bidirectional"))
    )
    (net (code "36") (name "Net-(R15-P$2)") (class "Default")
      (node (ref "C18") (pin "1") (pinfunction "1_1") (pintype "passive"))
      (node (ref "C19") (pin "2") (pinfunction "2_2") (pintype "passive"))
      (node (ref "R15") (pin "2") (pinfunction "P$2_2") (pintype "passive"))
      (node (ref "U5") (pin "3") (pinfunction "T-_3") (pintype "bidirectional"))
    )
    (net (code "37") (name "Net-(R16-P$2)") (class "Default")
      (node (ref "C19") (pin "1") (pinfunction "1_1") (pintype "passive"))
      (node (ref "C20") (pin "2") (pinfunction "2_2") (pintype "passive"))
      (node (ref "R16") (pin "2") (pinfunction "P$2_2") (pintype "passive"))
      (node (ref "U5") (pin "4") (pinfunction "T+_4") (pintype "bidirectional"))
    )
    (net (code "38") (name "Net-(R17-P$2)") (class "Default")
      (node (ref "C25") (pin "1") (pinfunction "1_1") (pintype "passive"))
      (node (ref "C26") (pin "2") (pinfunction "2_2") (pintype "passive"))
      (node (ref "R17") (pin "2") (pinfunction "P$2_2") (pintype "passive"))
      (node (ref "U6") (pin "3") (pinfunction "T-_3") (pintype "bidirectional"))
    )
    (net (code "39") (name "Net-(R18-P$2)") (class "Default")
      (node (ref "C26") (pin "1") (pinfunction "1_1") (pintype "passive"))
      (node (ref "C27") (pin "2") (pinfunction "2_2") (pintype "passive"))
      (node (ref "R18") (pin "2") (pinfunction "P$2_2") (pintype "passive"))
      (node (ref "U6") (pin "4") (pinfunction "T+_4") (pintype "bidirectional"))
    )
    (net (code "40") (name "Net-(R20-P$1)") (class "Default")
      (node (ref "R20") (pin "1") (pinfunction "P$1_1") (pintype "passive"))
      (node (ref "U7") (pin "23") (pinfunction "PC0(ADC0)_23") (pintype "bidirectional"))
    )
    (net (code "41") (name "Net-(R20-P$2)") (class "Default")
      (node (ref "D6") (pin "ANODE") (pinfunction "ANODE_ANODE") (pintype "power_in"))
      (node (ref "R20") (pin "2") (pinfunction "P$2_2") (pintype "passive"))
    )
    (net (code "42") (name "Net-(R21-P$1)") (class "Default")
      (node (ref "R21") (pin "1") (pinfunction "P$1_1") (pintype "passive"))
      (node (ref "U7") (pin "13") (pinfunction "PB1(OC1A)_13") (pintype "bidirectional"))
    )
    (net (code "43") (name "Net-(R21-P$2)") (class "Default")
      (node (ref "D7") (pin "ANODE") (pinfunction "ANODE_ANODE") (pintype "power_in"))
      (node (ref "R21") (pin "2") (pinfunction "P$2_2") (pintype "passive"))
    )
    (net (code "44") (name "Net-(U1-SW1)") (class "Default")
      (node (ref "L1") (pin "P$1") (pinfunction "P$1_P$1") (pintype "passive"))
      (node (ref "U1") (pin "4") (pinfunction "SW1_4") (pintype "bidirectional"))
    )
    (net (code "45") (name "Net-(U1-SW2)") (class "Default")
      (node (ref "L1") (pin "P$2") (pinfunction "P$2_P$2") (pintype "passive"))
      (node (ref "U1") (pin "2") (pinfunction "SW2_2") (pintype "bidirectional"))
    )
    (net (code "46") (name "Net-(U3-SS)") (class "Default")
      (node (ref "C8") (pin "1") (pinfunction "1_1") (pintype "passive"))
      (node (ref "U3") (pin "10") (pinfunction "SS_10") (pintype "bidirectional"))
    )
    (net (code "47") (name "Net-(U7-AREF)") (class "Default")
      (node (ref "C30") (pin "1") (pinfunction "1_1") (pintype "passive"))
      (node (ref "U7") (pin "20") (pinfunction "AREF_20") (pintype "bidirectional"))
    )
    (net (code "48") (name "Net-(U7-PB6(XTAL1{slash}TOSC1))") (class "Default")
      (node (ref "U7") (pin "7") (pinfunction "PB6(XTAL1/TOSC1)_7") (pintype "bidirectional"))
      (node (ref "Y1") (pin "1") (pinfunction "1_1") (pintype "passive"))
    )
    (net (code "49") (name "Net-(U7-PB7(XTAL2{slash}TOSC2))") (class "Default")
      (node (ref "U7") (pin "8") (pinfunction "PB7(XTAL2/TOSC2)_8") (pintype "bidirectional"))
      (node (ref "Y1") (pin "3") (pinfunction "3_3") (pintype "passive"))
    )
    (net (code "50") (name "Net-(U8-ANT)") (class "Default")
      (node (ref "ANT1") (pin "1") (pinfunction "1_1") (pintype "bidirectional"))
      (node (ref "U8") (pin "9") (pinfunction "ANT_9") (pintype "passive"))
    )
    (net (code "51") (name "Net-(U8-MOSI)") (class "Default")
      (node (ref "SJ2") (pin "2") (pinfunction "2_2") (pintype "passive"))
      (node (ref "U8") (pin "3") (pinfunction "MOSI_3") (pintype "input"))
    )
    (net (code "52") (name "Net-(U8-SCK)") (class "Default")
      (node (ref "SJ1") (pin "2") (pinfunction "2_2") (pintype "passive"))
      (node (ref "U8") (pin "4") (pinfunction "SCK_4") (pintype "input"))
    )
    (net (code "53") (name "Net-(U9-CLK)") (class "Default")
      (node (ref "SJ3") (pin "1") (pinfunction "1_1") (pintype "passive"))
      (node (ref "U9") (pin "6") (pinfunction "CLK_6") (pintype "bidirectional"))
    )
    (net (code "54") (name "Net-(U9-MOSI)") (class "Default")
      (node (ref "SJ4") (pin "1") (pinfunction "1_1") (pintype "passive"))
      (node (ref "U9") (pin "5") (pinfunction "MOSI_5") (pintype "bidirectional"))
    )
    (net (code "55") (name "PWR_GD") (class "Default")
      (node (ref "U2") (pin "6") (pinfunction "/PG_6") (pintype "output"))
      (node (ref "U7") (pin "27") (pinfunction "PC4(ADC4/SDA)_27") (pintype "bidirectional"))
    )
    (net (code "56") (name "RF_CS") (class "Default")
      (node (ref "U7") (pin "14") (pinfunction "PB2(SS/OC1B)_14") (pintype "bidirectional"))
      (node (ref "U8") (pin "5") (pinfunction "NSS_5") (pintype "input"))
    )
    (net (code "57") (name "RF_INT") (class "Default")
      (node (ref "U7") (pin "32") (pinfunction "PD2(INT0)_32") (pintype "bidirectional"))
      (node (ref "U8") (pin "14") (pinfunction "DIO0_14") (pintype "bidirectional"))
    )
    (net (code "58") (name "RST") (class "Default")
      (node (ref "C31") (pin "2") (pinfunction "2_2") (pintype "passive"))
      (node (ref "R19") (pin "2") (pinfunction "P$2_2") (pintype "passive"))
      (node (ref "TC1") (pin "P$5") (pinfunction "PIN5_P$5") (pintype "bidirectional"))
      (node (ref "U7") (pin "29") (pinfunction "PC6(/RESET)_29") (pintype "bidirectional"))
    )
    (net (code "59") (name "RX") (class "Default")
      (node (ref "J6") (pin "3") (pinfunction "TXO_3") (pintype "passive"))
      (node (ref "U7") (pin "30") (pinfunction "PD0(RXD)_30") (pintype "bidirectional"))
    )
    (net (code "60") (name "SCK") (class "Default")
      (node (ref "SJ1") (pin "1") (pinfunction "1_1") (pintype "passive"))
      (node (ref "SJ3") (pin "2") (pinfunction "2_2") (pintype "passive"))
      (node (ref "TC1") (pin "P$3") (pinfunction "PIN3_P$3") (pintype "bidirectional"))
      (node (ref "U4") (pin "10") (pinfunction "SCK_10") (pintype "bidirectional"))
      (node (ref "U5") (pin "10") (pinfunction "SCK_10") (pintype "bidirectional"))
      (node (ref "U6") (pin "10") (pinfunction "SCK_10") (pintype "bidirectional"))
      (node (ref "U7") (pin "17") (pinfunction "PB5(SCK)_17") (pintype "bidirectional"))
    )
    (net (code "61") (name "TC1_CS") (class "Default")
      (node (ref "U4") (pin "9") (pinfunction "CS_9") (pintype "bidirectional"))
      (node (ref "U7") (pin "11") (pinfunction "PD7(AIN1)_11") (pintype "bidirectional"))
    )
    (net (code "62") (name "TC2_CS") (class "Default")
      (node (ref "U6") (pin "9") (pinfunction "CS_9") (pintype "bidirectional"))
      (node (ref "U7") (pin "10") (pinfunction "PD6(AIN0)_10") (pintype "bidirectional"))
    )
    (net (code "63") (name "TC2_NEG") (class "Default")
      (node (ref "J5") (pin "NEG") (pinfunction "PIN1_NEG") (pintype "bidirectional"))
      (node (ref "R17") (pin "1") (pinfunction "P$1_1") (pintype "passive"))
      (node (ref "U6") (pin "2") (pinfunction "BIAS_2") (pintype "bidirectional"))
    )
    (net (code "64") (name "TC3_CS") (class "Default")
      (node (ref "U5") (pin "9") (pinfunction "CS_9") (pintype "bidirectional"))
      (node (ref "U7") (pin "9") (pinfunction "PD5(T1)_9") (pintype "bidirectional"))
    )
    (net (code "65") (name "TX") (class "Default")
      (node (ref "J6") (pin "2") (pinfunction "RXI_2") (pintype "passive"))
      (node (ref "U7") (pin "31") (pinfunction "PD1(TXD)_31") (pintype "bidirectional"))
    )
    (net (code "66") (name "V_BAT") (class "Default")
      (node (ref "BATT1") (pin "POS_1") (pinfunction "VBAT_POS_1") (pintype "bidirectional"))
      (node (ref "BATT1") (pin "POS_2") (pinfunction "VBAT_POS_2") (pintype "bidirectional"))
      (node (ref "BATT1") (pin "POS_3") (pinfunction "VBAT_POS_3") (pintype "bidirectional"))
      (node (ref "C1") (pin "1") (pinfunction "1_1") (pintype "passive"))
      (node (ref "C5") (pin "1") (pinfunction "1_1") (pintype "passive"))
      (node (ref "C6") (pin "2") (pinfunction "2_2") (pintype "passive"))
      (node (ref "C7") (pin "1") (pinfunction "1_1") (pintype "passive"))
      (node (ref "L2") (pin "1") (pinfunction "P$1_1") (pintype "passive"))
      (node (ref "Q3") (pin "2") (pinfunction "S_2") (pintype "passive"))
      (node (ref "R22") (pin "2") (pinfunction "P$2_2") (pintype "passive"))
      (node (ref "U1") (pin "5") (pinfunction "PVIN_5") (pintype "bidirectional"))
      (node (ref "U1") (pin "6") (pinfunction "EN_6") (pintype "bidirectional"))
      (node (ref "U1") (pin "8") (pinfunction "VIN_8") (pintype "bidirectional"))
      (node (ref "U2") (pin "14") (pinfunction "VBAT1_14") (pintype "output"))
      (node (ref "U2") (pin "15") (pinfunction "VBAT2_15") (pintype "output"))
      (node (ref "U2") (pin "16") (pinfunction "VBAT3_16") (pintype "output"))
      (node (ref "U3") (pin "8") (pinfunction "VIN_8") (pintype "bidirectional"))
    )
    (net (code "67") (name "V_LOAD") (class "Default")
      (node (ref "C4") (pin "1") (pinfunction "1_1") (pintype "passive"))
      (node (ref "U2") (pin "1") (pinfunction "OUT1_1") (pintype "output"))
      (node (ref "U2") (pin "20") (pinfunction "OUT2_20") (pintype "output"))
    )
    (net (code "68") (name "V_SOLAR") (class "Default")
      (node (ref "C11") (pin "POS") (pinfunction "POS_POS") (pintype "passive"))
      (node (ref "C12") (pin "1") (pinfunction "1_1") (pintype "passive"))
      (node (ref "D4") (pin "C") (pinfunction "C_C") (pintype "passive"))
      (node (ref "R4") (pin "2") (pinfunction "P$2_2") (pintype "passive"))
      (node (ref "U2") (pin "17") (pinfunction "CE_17") (pintype "input"))
      (node (ref "U2") (pin "18") (pinfunction "IN1_18") (pintype "input"))
      (node (ref "U2") (pin "19") (pinfunction "IN2_19") (pintype "input"))
      (node (ref "U2") (pin "3") (pinfunction "SEL_3") (pintype "input"))
      (node (ref "U2") (pin "4") (pinfunction "PROG2_4") (pintype "input"))
      (node (ref "U2") (pin "9") (pinfunction "/TE_9") (pintype "input"))
    )
    (net (code "69") (name "unconnected-(J6-CTS-Pad5)") (class "Default")
      (node (ref "J6") (pin "5") (pinfunction "CTS_5") (pintype "passive"))
    )
    (net (code "70") (name "unconnected-(U2-STAT1{slash}LBO-Pad8)") (class "Default")
      (node (ref "U2") (pin "8") (pinfunction "STAT1/LBO_8") (pintype "output"))
    )
    (net (code "71") (name "unconnected-(U2-STAT2-Pad7)") (class "Default")
      (node (ref "U2") (pin "7") (pinfunction "STAT2_7") (pintype "output"))
    )
    (net (code "72") (name "unconnected-(U4-DNC-Pad6)") (class "Default")
      (node (ref "U4") (pin "6") (pinfunction "DNC_6") (pintype "bidirectional"))
    )
    (net (code "73") (name "unconnected-(U4-DRDY-Pad7)") (class "Default")
      (node (ref "U4") (pin "7") (pinfunction "DRDY_7") (pintype "bidirectional"))
    )
    (net (code "74") (name "unconnected-(U4-FAULT-Pad13)") (class "Default")
      (node (ref "U4") (pin "13") (pinfunction "FAULT_13") (pintype "bidirectional"))
    )
    (net (code "75") (name "unconnected-(U5-DNC-Pad6)") (class "Default")
      (node (ref "U5") (pin "6") (pinfunction "DNC_6") (pintype "bidirectional"))
    )
    (net (code "76") (name "unconnected-(U5-DRDY-Pad7)") (class "Default")
      (node (ref "U5") (pin "7") (pinfunction "DRDY_7") (pintype "bidirectional"))
    )
    (net (code "77") (name "unconnected-(U5-FAULT-Pad13)") (class "Default")
      (node (ref "U5") (pin "13") (pinfunction "FAULT_13") (pintype "bidirectional"))
    )
    (net (code "78") (name "unconnected-(U6-DNC-Pad6)") (class "Default")
      (node (ref "U6") (pin "6") (pinfunction "DNC_6") (pintype "bidirectional"))
    )
    (net (code "79") (name "unconnected-(U6-DRDY-Pad7)") (class "Default")
      (node (ref "U6") (pin "7") (pinfunction "DRDY_7") (pintype "bidirectional"))
    )
    (net (code "80") (name "unconnected-(U6-FAULT-Pad13)") (class "Default")
      (node (ref "U6") (pin "13") (pinfunction "FAULT_13") (pintype "bidirectional"))
    )
    (net (code "81") (name "unconnected-(U8-DIO1-Pad15)") (class "Default")
      (node (ref "U8") (pin "15") (pinfunction "DIO1_15") (pintype "bidirectional"))
    )
    (net (code "82") (name "unconnected-(U8-DIO2-Pad16)") (class "Default")
      (node (ref "U8") (pin "16") (pinfunction "DIO2_16") (pintype "bidirectional"))
    )
    (net (code "83") (name "unconnected-(U8-DIO3-Pad11)") (class "Default")
      (node (ref "U8") (pin "11") (pinfunction "DIO3_11") (pintype "bidirectional"))
    )
    (net (code "84") (name "unconnected-(U8-DIO4-Pad12)") (class "Default")
      (node (ref "U8") (pin "12") (pinfunction "DIO4_12") (pintype "bidirectional"))
    )
    (net (code "85") (name "unconnected-(U8-DIO5-Pad7)") (class "Default")
      (node (ref "U8") (pin "7") (pinfunction "DIO5_7") (pintype "bidirectional"))
    )
    (net (code "86") (name "unconnected-(U8-RESET-Pad6)") (class "Default")
      (node (ref "U8") (pin "6") (pinfunction "RESET_6") (pintype "input"))
    )
  )
)
